# schematic.net
KiCad netlist of a schematic drawn in EasyEDA
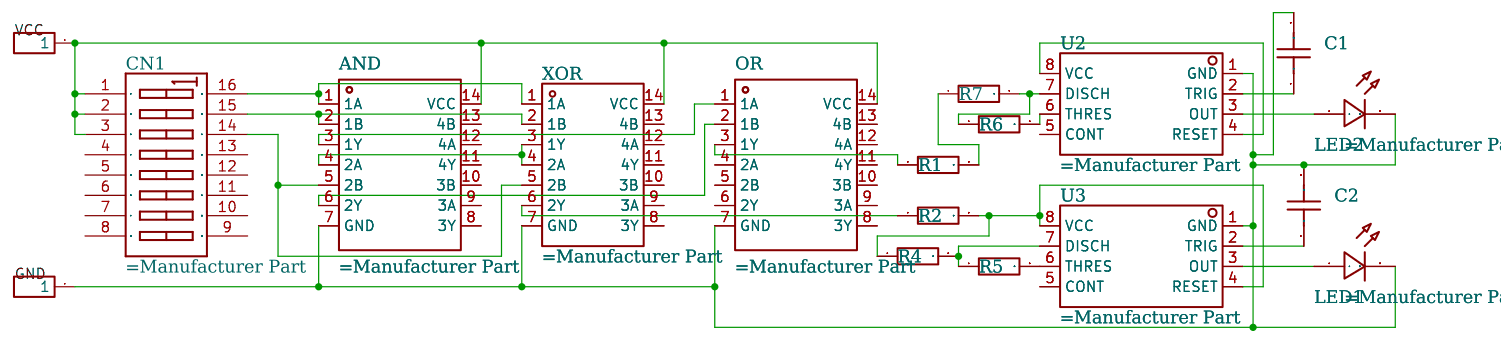
[diagram p0: schematic sheet]

(export (version "E")
  (design (tool "Eeschema 10.0.6"))
  (components
    (comp (ref "AND")
      (value "=Manufacturer Part")
      (fields (field (name "Manufacturer Part") "SN74HC08N") (field (name "Manufacturer") "TI(德州仪器)"))
      (libsource (lib "") (part "Unknown_440_-670"))
    )
    (comp (ref "C1")
      (value "100uF")
      (fields
        (field (name "Manufacturer Part") "50YXJ100MT78X11.5")
        (field (name "Manufacturer") "rubycon(红宝石)")
      )
      (libsource (lib "") (part "Unknown_880_-725"))
    )
    (comp (ref "C2")
      (value "100uF")
      (fields
        (field (name "Manufacturer Part") "50YXJ100MT78X11.5")
        (field (name "Manufacturer") "rubycon(红宝石)")
      )
      (libsource (lib "") (part "Unknown_885_-650"))
    )
    (comp (ref "CN1")
      (value "=Manufacturer Part")
      (fields (field (name "Manufacturer Part") "DS-08RP") (field (name "Manufacturer") "韩国韩荣"))
      (libsource (lib "") (part "Unknown_325_-665"))
    )
    (comp (ref "H1")
      (value "=Manufacturer Part")
      (fields (field (name "Manufacturer Part") "2059-301/998-403") (field (name "Manufacturer") "WAGO(万可)"))
      (libsource (lib "") (part "Unknown_260_-610"))
    )
    (comp (ref "H2")
      (value "=Manufacturer Part")
      (fields (field (name "Manufacturer Part") "2059-301/998-403") (field (name "Manufacturer") "WAGO(万可)"))
      (libsource (lib "") (part "Unknown_260_-730"))
    )
    (comp (ref "LED1")
      (value "=Manufacturer Part")
      (fields (field (name "Manufacturer Part") "LTL-4231N") (field (name "Manufacturer") "LITEON(光宝)"))
      (libsource (lib "") (part "Unknown_910_-620"))
    )
    (comp (ref "LED2")
      (value "=Manufacturer Part")
      (fields (field (name "Manufacturer Part") "LTL-4231N") (field (name "Manufacturer") "LITEON(光宝)"))
      (libsource (lib "") (part "Unknown_910_-695"))
    )
    (comp (ref "OR")
      (value "=Manufacturer Part")
      (fields (field (name "Manufacturer Part") "SN74HC32N") (field (name "Manufacturer") "TI(德州仪器)"))
      (libsource (lib "") (part "Unknown_635_-670"))
    )
    (comp (ref "R1")
      (value "1kΩ")
      (fields (field (name "Manufacturer Part") "RC0402JR-071KL") (field (name "Manufacturer") "YAGEO(国巨)"))
      (libsource (lib "") (part "Unknown_705_-670"))
    )
    (comp (ref "R2")
      (value "1kΩ")
      (fields (field (name "Manufacturer Part") "RC0402JR-071KL") (field (name "Manufacturer") "YAGEO(国巨)"))
      (libsource (lib "") (part "Unknown_705_-645"))
    )
    (comp (ref "R4")
      (value "1kΩ")
      (fields (field (name "Manufacturer Part") "RC0402JR-071KL") (field (name "Manufacturer") "YAGEO(国巨)"))
      (libsource (lib "") (part "Unknown_695_-625"))
    )
    (comp (ref "R5")
      (value "1kΩ")
      (fields (field (name "Manufacturer Part") "RC0402JR-071KL") (field (name "Manufacturer") "YAGEO(国巨)"))
      (libsource (lib "") (part "Unknown_735_-620"))
    )
    (comp (ref "R6")
      (value "1kΩ")
      (fields (field (name "Manufacturer Part") "RC0402JR-071KL") (field (name "Manufacturer") "YAGEO(国巨)"))
      (libsource (lib "") (part "Unknown_735_-690"))
    )
    (comp (ref "R7")
      (value "1kΩ")
      (fields (field (name "Manufacturer Part") "RC0402JR-071KL") (field (name "Manufacturer") "YAGEO(国巨)"))
      (libsource (lib "") (part "Unknown_725_-705"))
    )
    (comp (ref "U2")
      (value "=Manufacturer Part")
      (fields (field (name "Manufacturer Part") "LM555N") (field (name "Manufacturer") "HGSEMI(华冠)"))
      (libsource (lib "") (part "Unknown_805_-700"))
    )
    (comp (ref "U3")
      (value "=Manufacturer Part")
      (fields (field (name "Manufacturer Part") "LM555N") (field (name "Manufacturer") "HGSEMI(华冠)"))
      (libsource (lib "") (part "Unknown_805_-625"))
    )
    (comp (ref "XOR")
      (value "=Manufacturer Part")
      (fields (field (name "Manufacturer Part") "SN74HC86N") (field (name "Manufacturer") "TI(德州仪器)"))
      (libsource (lib "") (part "Unknown_535_-670"))
    )
  )
  (nets
    (net (code "3") (name "Net-(AND-1A)") (class "Default")
      (node (ref "AND") (pin "1") (pinfunction "1A_1") (pintype "unspecified"))
      (node (ref "CN1") (pin "16") (pinfunction "16_16") (pintype "unspecified"))
      (node (ref "XOR") (pin "1") (pinfunction "1A_1") (pintype "unspecified"))
    )
    (net (code "4") (name "Net-(AND-1B)") (class "Default")
      (node (ref "AND") (pin "2") (pinfunction "1B_2") (pintype "unspecified"))
      (node (ref "CN1") (pin "15") (pinfunction "15_15") (pintype "unspecified"))
      (node (ref "XOR") (pin "2") (pinfunction "1B_2") (pintype "unspecified"))
    )
    (net (code "5") (name "Net-(AND-1Y)") (class "Default")
      (node (ref "AND") (pin "3") (pinfunction "1Y_3") (pintype "unspecified"))
      (node (ref "OR") (pin "1") (pinfunction "1A_1") (pintype "unspecified"))
    )
    (net (code "6") (name "Net-(AND-2A)") (class "Default")
      (node (ref "AND") (pin "4") (pinfunction "2A_4") (pintype "unspecified"))
      (node (ref "XOR") (pin "3") (pinfunction "1Y_3") (pintype "unspecified"))
      (node (ref "XOR") (pin "4") (pinfunction "2A_4") (pintype "unspecified"))
    )
    (net (code "7") (name "Net-(AND-2B)") (class "Default")
      (node (ref "AND") (pin "5") (pinfunction "2B_5") (pintype "unspecified"))
      (node (ref "CN1") (pin "14") (pinfunction "14_14") (pintype "unspecified"))
      (node (ref "XOR") (pin "5") (pinfunction "2B_5") (pintype "unspecified"))
    )
    (net (code "8") (name "Net-(AND-2Y)") (class "Default")
      (node (ref "AND") (pin "6") (pinfunction "2Y_6") (pintype "unspecified"))
      (node (ref "OR") (pin "2") (pinfunction "1B_2") (pintype "unspecified"))
    )
    (net (code "9") (name "Net-(AND-GND)") (class "Default")
      (node (ref "AND") (pin "7") (pinfunction "GND_7") (pintype "unspecified"))
      (node (ref "C1") (pin "2") (pinfunction "2_2") (pintype "unspecified"))
      (node (ref "C2") (pin "2") (pinfunction "2_2") (pintype "unspecified"))
      (node (ref "H1") (pin "1") (pinfunction "1_1") (pintype "unspecified"))
      (node (ref "LED1") (pin "2") (pinfunction "C_2") (pintype "unspecified"))
      (node (ref "LED2") (pin "2") (pinfunction "C_2") (pintype "unspecified"))
      (node (ref "OR") (pin "7") (pinfunction "GND_7") (pintype "unspecified"))
      (node (ref "U2") (pin "1") (pinfunction "GND_1") (pintype "unspecified"))
      (node (ref "U3") (pin "1") (pinfunction "GND_1") (pintype "unspecified"))
      (node (ref "XOR") (pin "7") (pinfunction "GND_7") (pintype "unspecified"))
    )
    (net (code "10") (name "Net-(AND-VCC)") (class "Default")
      (node (ref "AND") (pin "14") (pinfunction "VCC_14") (pintype "unspecified"))
      (node (ref "CN1") (pin "1") (pinfunction "A1_1") (pintype "unspecified"))
      (node (ref "CN1") (pin "2") (pinfunction "A2_2") (pintype "unspecified"))
      (node (ref "CN1") (pin "3") (pinfunction "A3_3") (pintype "unspecified"))
      (node (ref "H2") (pin "1") (pinfunction "1_1") (pintype "unspecified"))
      (node (ref "OR") (pin "14") (pinfunction "VCC_14") (pintype "unspecified"))
      (node (ref "XOR") (pin "14") (pinfunction "VCC_14") (pintype "unspecified"))
    )
    (net (code "11") (name "Net-(LED1-A)") (class "Default")
      (node (ref "LED1") (pin "1") (pinfunction "A_1") (pintype "unspecified"))
      (node (ref "U3") (pin "3") (pinfunction "OUT_3") (pintype "unspecified"))
    )
    (net (code "12") (name "Net-(LED2-A)") (class "Default")
      (node (ref "LED2") (pin "1") (pinfunction "A_1") (pintype "unspecified"))
      (node (ref "U2") (pin "3") (pinfunction "OUT_3") (pintype "unspecified"))
    )
    (net (code "13") (name "Net-(OR-1Y)") (class "Default")
      (node (ref "OR") (pin "3") (pinfunction "1Y_3") (pintype "unspecified"))
      (node (ref "R1") (pin "1") (pinfunction "1_1") (pintype "unspecified"))
    )
    (net (code "14") (name "Net-(R1-Pad2)") (class "Default")
      (node (ref "R1") (pin "2") (pinfunction "2_2") (pintype "unspecified"))
      (node (ref "R7") (pin "1") (pinfunction "1_1") (pintype "unspecified"))
    )
    (net (code "15") (name "Net-(U2-DISCH)") (class "Default")
      (node (ref "R6") (pin "1") (pinfunction "1_1") (pintype "unspecified"))
      (node (ref "R7") (pin "2") (pinfunction "2_2") (pintype "unspecified"))
      (node (ref "U2") (pin "7") (pinfunction "DISCH_7") (pintype "unspecified"))
    )
    (net (code "16") (name "Net-(U2-RESET)") (class "Default")
      (node (ref "U2") (pin "4") (pinfunction "RESET_4") (pintype "unspecified"))
      (node (ref "U2") (pin "8") (pinfunction "VCC_8") (pintype "unspecified"))
    )
    (net (code "17") (name "Net-(U2-THRES)") (class "Default")
      (node (ref "R6") (pin "2") (pinfunction "2_2") (pintype "unspecified"))
      (node (ref "U2") (pin "6") (pinfunction "THRES_6") (pintype "unspecified"))
    )
    (net (code "18") (name "Net-(U2-TRIG)") (class "Default")
      (node (ref "C1") (pin "1") (pinfunction "1_1") (pintype "unspecified"))
      (node (ref "U2") (pin "2") (pinfunction "TRIG_2") (pintype "unspecified"))
    )
    (net (code "19") (name "Net-(U3-DISCH)") (class "Default")
      (node (ref "R4") (pin "2") (pinfunction "2_2") (pintype "unspecified"))
      (node (ref "R5") (pin "1") (pinfunction "1_1") (pintype "unspecified"))
      (node (ref "U3") (pin "7") (pinfunction "DISCH_7") (pintype "unspecified"))
    )
    (net (code "20") (name "Net-(U3-RESET)") (class "Default")
      (node (ref "R2") (pin "2") (pinfunction "2_2") (pintype "unspecified"))
      (node (ref "R4") (pin "1") (pinfunction "1_1") (pintype "unspecified"))
      (node (ref "U3") (pin "4") (pinfunction "RESET_4") (pintype "unspecified"))
      (node (ref "U3") (pin "8") (pinfunction "VCC_8") (pintype "unspecified"))
    )
    (net (code "21") (name "Net-(U3-THRES)") (class "Default")
      (node (ref "R5") (pin "2") (pinfunction "2_2") (pintype "unspecified"))
      (node (ref "U3") (pin "6") (pinfunction "THRES_6") (pintype "unspecified"))
    )
    (net (code "22") (name "Net-(U3-TRIG)") (class "Default")
      (node (ref "C2") (pin "1") (pinfunction "1_1") (pintype "unspecified"))
      (node (ref "U3") (pin "2") (pinfunction "TRIG_2") (pintype "unspecified"))
    )
    (net (code "23") (name "Net-(XOR-2Y)") (class "Default")
      (node (ref "R2") (pin "1") (pinfunction "1_1") (pintype "unspecified"))
      (node (ref "XOR") (pin "6") (pinfunction "2Y_6") (pintype "unspecified"))
    )
    (net (code "24") (name "unconnected-(AND-3A-Pad9)") (class "Default")
      (node (ref "AND") (pin "9") (pinfunction "3A_9") (pintype "unspecified"))
    )
    (net (code "25") (name "unconnected-(AND-3B-Pad10)") (class "Default")
      (node (ref "AND") (pin "10") (pinfunction "3B_10") (pintype "unspecified"))
    )
    (net (code "26") (name "unconnected-(AND-3Y-Pad8)") (class "Default")
      (node (ref "AND") (pin "8") (pinfunction "3Y_8") (pintype "unspecified"))
    )
    (net (code "27") (name "unconnected-(AND-4A-Pad12)") (class "Default")
      (node (ref "AND") (pin "12") (pinfunction "4A_12") (pintype "unspecified"))
    )
    (net (code "28") (name "unconnected-(AND-4B-Pad13)") (class "Default")
      (node (ref "AND") (pin "13") (pinfunction "4B_13") (pintype "unspecified"))
    )
    (net (code "29") (name "unconnected-(AND-4Y-Pad11)") (class "Default")
      (node (ref "AND") (pin "11") (pinfunction "4Y_11") (pintype "unspecified"))
    )
    (net (code "30") (name "unconnected-(CN1-A4-Pad4)") (class "Default")
      (node (ref "CN1") (pin "4") (pinfunction "A4_4") (pintype "unspecified"))
    )
    (net (code "31") (name "unconnected-(CN1-A5-Pad5)") (class "Default")
      (node (ref "CN1") (pin "5") (pinfunction "A5_5") (pintype "unspecified"))
    )
    (net (code "32") (name "unconnected-(CN1-A6-Pad6)") (class "Default")
      (node (ref "CN1") (pin "6") (pinfunction "A6_6") (pintype "unspecified"))
    )
    (net (code "33") (name "unconnected-(CN1-A7-Pad7)") (class "Default")
      (node (ref "CN1") (pin "7") (pinfunction "A7_7") (pintype "unspecified"))
    )
    (net (code "34") (name "unconnected-(CN1-A8-Pad8)") (class "Default")
      (node (ref "CN1") (pin "8") (pinfunction "A8_8") (pintype "unspecified"))
    )
    (net (code "35") (name "unconnected-(CN1-Pad9)") (class "Default")
      (node (ref "CN1") (pin "9") (pinfunction "9_9") (pintype "unspecified"))
    )
    (net (code "36") (name "unconnected-(CN1-Pad10)") (class "Default")
      (node (ref "CN1") (pin "10") (pinfunction "10_10") (pintype "unspecified"))
    )
    (net (code "37") (name "unconnected-(CN1-Pad11)") (class "Default")
      (node (ref "CN1") (pin "11") (pinfunction "11_11") (pintype "unspecified"))
    )
    (net (code "38") (name "unconnected-(CN1-Pad12)") (class "Default")
      (node (ref "CN1") (pin "12") (pinfunction "12_12") (pintype "unspecified"))
    )
    (net (code "39") (name "unconnected-(CN1-Pad13)") (class "Default")
      (node (ref "CN1") (pin "13") (pinfunction "13_13") (pintype "unspecified"))
    )
    (net (code "40") (name "unconnected-(OR-2A-Pad4)") (class "Default")
      (node (ref "OR") (pin "4") (pinfunction "2A_4") (pintype "unspecified"))
    )
    (net (code "41") (name "unconnected-(OR-2B-Pad5)") (class "Default")
      (node (ref "OR") (pin "5") (pinfunction "2B_5") (pintype "unspecified"))
    )
    (net (code "42") (name "unconnected-(OR-2Y-Pad6)") (class "Default")
      (node (ref "OR") (pin "6") (pinfunction "2Y_6") (pintype "unspecified"))
    )
    (net (code "43") (name "unconnected-(OR-3A-Pad9)") (class "Default")
      (node (ref "OR") (pin "9") (pinfunction "3A_9") (pintype "unspecified"))
    )
    (net (code "44") (name "unconnected-(OR-3B-Pad10)") (class "Default")
      (node (ref "OR") (pin "10") (pinfunction "3B_10") (pintype "unspecified"))
    )
    (net (code "45") (name "unconnected-(OR-3Y-Pad8)") (class "Default")
      (node (ref "OR") (pin "8") (pinfunction "3Y_8") (pintype "unspecified"))
    )
    (net (code "46") (name "unconnected-(OR-4A-Pad12)") (class "Default")
      (node (ref "OR") (pin "12") (pinfunction "4A_12") (pintype "unspecified"))
    )
    (net (code "47") (name "unconnected-(OR-4B-Pad13)") (class "Default")
      (node (ref "OR") (pin "13") (pinfunction "4B_13") (pintype "unspecified"))
    )
    (net (code "48") (name "unconnected-(OR-4Y-Pad11)") (class "Default")
      (node (ref "OR") (pin "11") (pinfunction "4Y_11") (pintype "unspecified"))
    )
    (net (code "49") (name "unconnected-(U2-CONT-Pad5)") (class "Default")
      (node (ref "U2") (pin "5") (pinfunction "CONT_5") (pintype "unspecified"))
    )
    (net (code "50") (name "unconnected-(U3-CONT-Pad5)") (class "Default")
      (node (ref "U3") (pin "5") (pinfunction "CONT_5") (pintype "unspecified"))
    )
    (net (code "51") (name "unconnected-(XOR-3A-Pad9)") (class "Default")
      (node (ref "XOR") (pin "9") (pinfunction "3A_9") (pintype "unspecified"))
    )
    (net (code "52") (name "unconnected-(XOR-3B-Pad10)") (class "Default")
      (node (ref "XOR") (pin "10") (pinfunction "3B_10") (pintype "unspecified"))
    )
    (net (code "53") (name "unconnected-(XOR-3Y-Pad8)") (class "Default")
      (node (ref "XOR") (pin "8") (pinfunction "3Y_8") (pintype "unspecified"))
    )
    (net (code "54") (name "unconnected-(XOR-4A-Pad12)") (class "Default")
      (node (ref "XOR") (pin "12") (pinfunction "4A_12") (pintype "unspecified"))
    )
    (net (code "55") (name "unconnected-(XOR-4B-Pad13)") (class "Default")
      (node (ref "XOR") (pin "13") (pinfunction "4B_13") (pintype "unspecified"))
    )
    (net (code "56") (name "unconnected-(XOR-4Y-Pad11)") (class "Default")
      (node (ref "XOR") (pin "11") (pinfunction "4Y_11") (pintype "unspecified"))
    )
  )
)
